# SparkFun_Thing_Plus_RA6M5.net
KiCad netlist of a schematic drawn in EAGLE
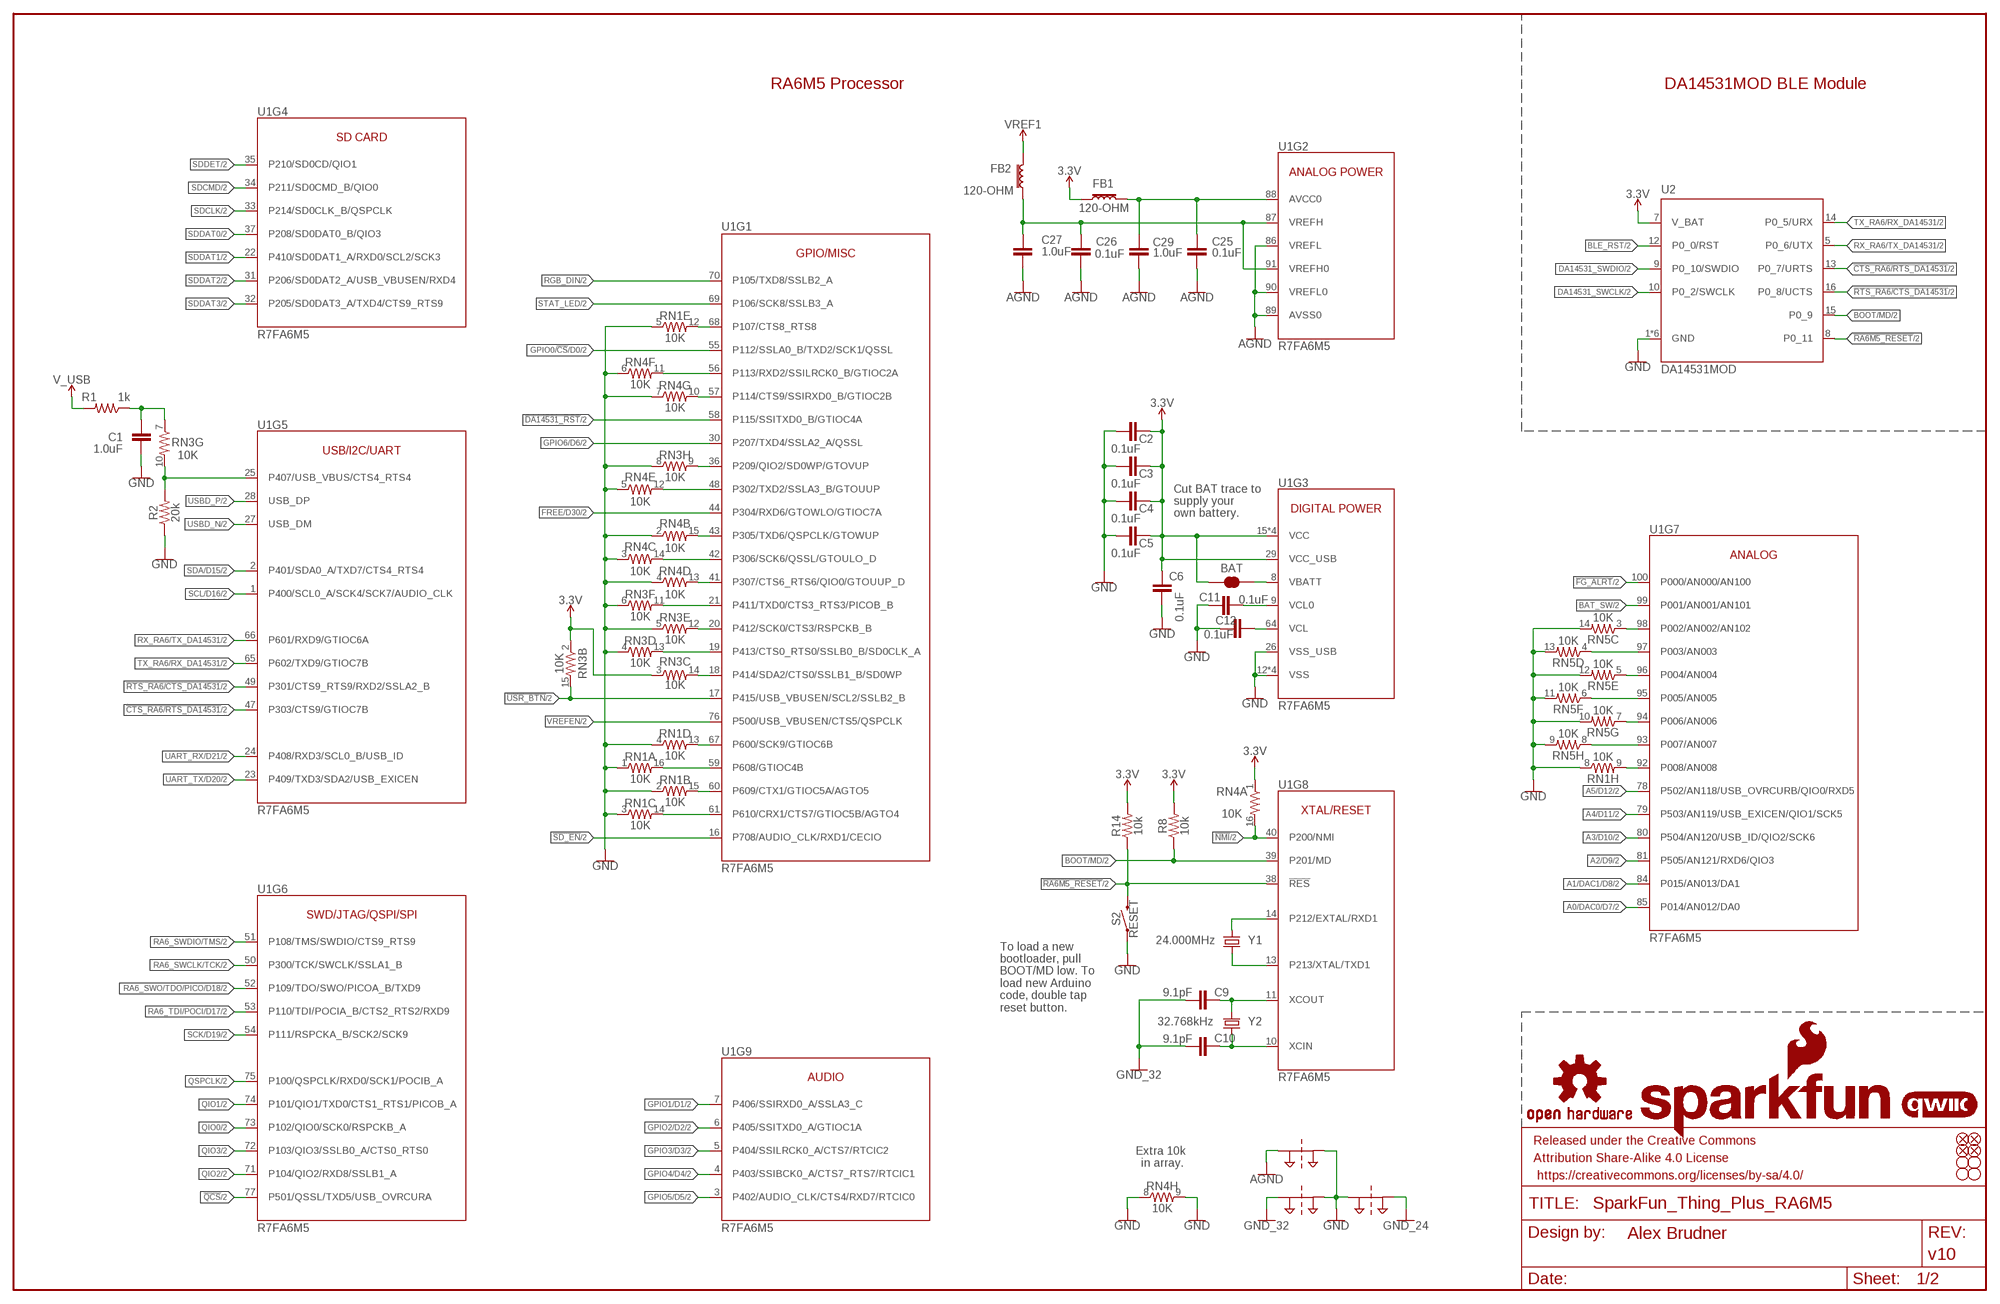
[diagram p0: schematic, sheet 1]
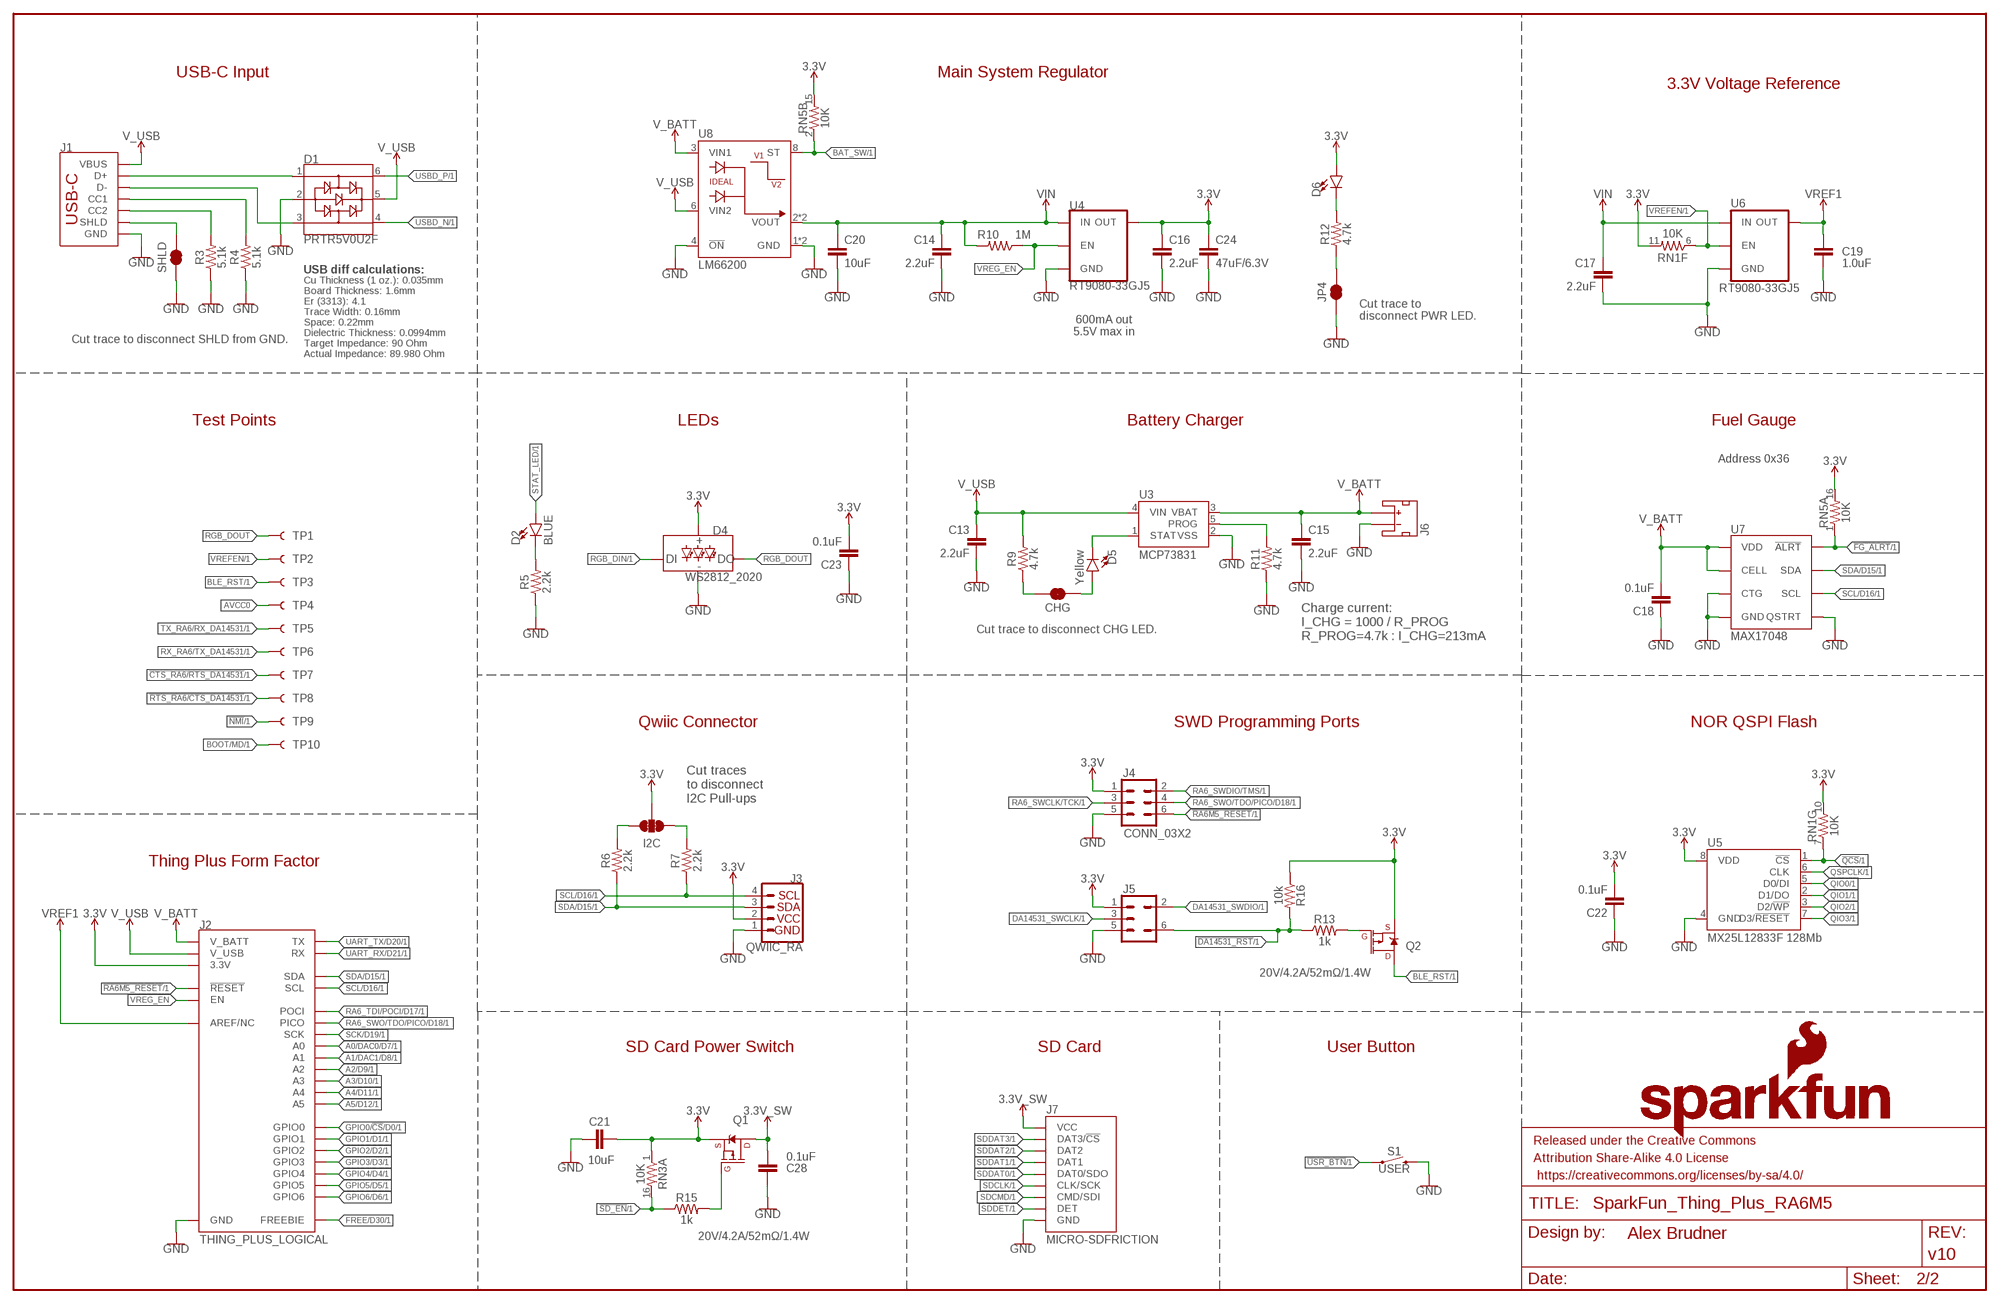
[diagram p1: schematic, sheet 2]

(export (version "E")
  (design (tool "Eeschema 10.0.6"))
  (components
    (comp (ref "C13")
      (value "2.2uF")
      (footprint "eagle-import:0402-TIGHT")
      (libsource (lib "eagle-import") (part "2.2UF-0402_TIGHT-10V-10%-X5R"))
    )
    (comp (ref "C14")
      (value "2.2uF")
      (footprint "eagle-import:0402-TIGHT")
      (libsource (lib "eagle-import") (part "2.2UF-0402_TIGHT-10V-10%-X5R"))
    )
    (comp (ref "C15")
      (value "2.2uF")
      (footprint "eagle-import:0402-TIGHT")
      (libsource (lib "eagle-import") (part "2.2UF-0402_TIGHT-10V-10%-X5R"))
    )
    (comp (ref "C16")
      (value "2.2uF")
      (footprint "eagle-import:0402-TIGHT")
      (libsource (lib "eagle-import") (part "2.2UF-0402_TIGHT-10V-10%-X5R"))
    )
    (comp (ref "C17")
      (value "2.2uF")
      (footprint "eagle-import:0402-TIGHT")
      (libsource (lib "eagle-import") (part "2.2UF-0402_TIGHT-10V-10%-X5R"))
    )
    (comp (ref "C18")
      (value "0.1uF")
      (footprint "eagle-import:0402-TIGHT")
      (libsource (lib "eagle-import") (part "0.1UF-0402T-16V-10%"))
    )
    (comp (ref "C19")
      (value "1.0uF")
      (footprint "eagle-import:0402-TIGHT")
      (libsource (lib "eagle-import") (part "1.0UF-0402T-16V-10%"))
    )
    (comp (ref "C20")
      (value "10uF")
      (footprint "eagle-import:0805")
      (libsource (lib "eagle-import") (part "10UF-0805-25V-10%"))
    )
    (comp (ref "C21")
      (value "10uF")
      (footprint "eagle-import:0805")
      (libsource (lib "eagle-import") (part "10UF-0805-25V-10%"))
    )
    (comp (ref "C22")
      (value "0.1uF")
      (footprint "eagle-import:0402-TIGHT")
      (libsource (lib "eagle-import") (part "0.1UF-0402T-16V-10%"))
    )
    (comp (ref "C23")
      (value "0.1uF")
      (footprint "eagle-import:0402-TIGHT")
      (libsource (lib "eagle-import") (part "0.1UF-0402T-16V-10%"))
    )
    (comp (ref "C24")
      (value "47uF/6.3V")
      (footprint "eagle-import:0805")
      (libsource (lib "eagle-import") (part "47UF"))
    )
    (comp (ref "C28")
      (value "0.1uF")
      (footprint "eagle-import:0402-TIGHT")
      (libsource (lib "eagle-import") (part "0.1UF-0402T-16V-10%"))
    )
    (comp (ref "CHG")
      (value "JUMPER-SMT_2_NC_TRACE_SILK")
      (footprint "eagle-import:SMT-JUMPER_2_NC_TRACE_SILK")
      (libsource (lib "eagle-import") (part "JUMPER-SMT_2_NC_TRACE_SILK"))
    )
    (comp (ref "D1")
      (value "PRTR5V0U2F")
      (footprint "eagle-import:SOT886")
      (libsource (lib "eagle-import") (part "PRTR5V0U2F"))
    )
    (comp (ref "D2")
      (value "BLUE")
      (footprint "eagle-import:LED-0603")
      (libsource (lib "eagle-import") (part "LED-BLUE0603"))
    )
    (comp (ref "D4")
      (value "WS2812_2020")
      (footprint "eagle-import:WS2812-2020")
      (libsource (lib "eagle-import") (part "WS2812_2020"))
    )
    (comp (ref "D5")
      (value "Yellow")
      (footprint "eagle-import:LED-0603")
      (libsource (lib "eagle-import") (part "LED-YELLOW0603"))
    )
    (comp (ref "D6")
      (value "LED-RED_0603-KB")
      (footprint "eagle-import:LED-0603")
      (libsource (lib "eagle-import") (part "LED-RED_0603-KB"))
    )
    (comp (ref "FRAME2")
      (value "FRAME-LEDGERNO_FOOTPRINT")
      (footprint "eagle-import:DUMMY")
      (fields (field (name "DESIGNER") "Alex Brudner") (field (name "REV") "v10"))
      (libsource (lib "eagle-import") (part "FRAME-LEDGERNO_FOOTPRINT"))
    )
    (comp (ref "I2C")
      (value "JUMPER-SMT_3_2-NC_TRACE_SILK")
      (footprint "eagle-import:SMT-JUMPER_3_2-NC_TRACE_SILK")
      (libsource (lib "eagle-import") (part "JUMPER-SMT_3_2-NC_TRACE_SILK"))
    )
    (comp (ref "J1")
      (value "USB Female Type C Connector")
      (footprint "eagle-import:USB-C-16P-6LAYER-ISOLATED")
      (libsource (lib "eagle-import") (part "USB_C_6-LAYER-ISOLATED"))
    )
    (comp (ref "J2")
      (value "THING_PLUS_LOGICAL")
      (footprint "eagle-import:THING_PLUS")
      (libsource (lib "eagle-import") (part "THING_PLUS_LOGICAL"))
    )
    (comp (ref "J3")
      (value "QWIIC_RA")
      (footprint "eagle-import:JST04_1MM_RA")
      (libsource (lib "eagle-import") (part "QWIIC_CONNECTORJS-1MM"))
    )
    (comp (ref "J4")
      (value "CONN_03X2")
      (footprint "eagle-import:PAD_05_03X2_TP")
      (libsource (lib "eagle-import") (part "CONN_03X2"))
    )
    (comp (ref "J5")
      (value "SWD-5PIN")
      (footprint "eagle-import:PAD_05_03X2_TP_NO4")
      (libsource (lib "eagle-import") (part "SWD-5PIN"))
    )
    (comp (ref "J6")
      (value "JST_2MM_MALE")
      (footprint "eagle-import:JST-2-SMD")
      (libsource (lib "eagle-import") (part "JST_2MM_MALE"))
    )
    (comp (ref "J7")
      (value "MICRO-SDFRICTION")
      (footprint "eagle-import:MICROSD_TINY")
      (libsource (lib "eagle-import") (part "MICRO-SDFRICTION"))
    )
    (comp (ref "JP4")
      (value "JUMPER-SMT_2_NC_TRACE_SILK")
      (footprint "eagle-import:SMT-JUMPER_2_NC_TRACE_SILK")
      (libsource (lib "eagle-import") (part "JUMPER-SMT_2_NC_TRACE_SILK"))
    )
    (comp (ref "LOGO4")
      (value "SFE_LOGO_NAME_FLAMEBLANK")
      (footprint "eagle-import:BLANK")
      (libsource (lib "eagle-import") (part "SFE_LOGO_NAME_FLAMEBLANK"))
    )
    (comp (ref "Q1")
      (value "20V/4.2A/52mΩ/1.4W")
      (footprint "eagle-import:SOT23-3")
      (libsource (lib "eagle-import") (part "MOSFET_PCH-DMG2305UX-7"))
    )
    (comp (ref "Q2")
      (value "20V/4.2A/52mΩ/1.4W")
      (footprint "eagle-import:SOT23-3")
      (libsource (lib "eagle-import") (part "MOSFET_PCH-DMG2305UX-7"))
    )
    (comp (ref "R3")
      (value "5.1k")
      (footprint "eagle-import:0402-TIGHT")
      (libsource (lib "eagle-import") (part "5.1KOHM-0402T-1/16W-1%"))
    )
    (comp (ref "R4")
      (value "5.1k")
      (footprint "eagle-import:0402-TIGHT")
      (libsource (lib "eagle-import") (part "5.1KOHM-0402T-1/16W-1%"))
    )
    (comp (ref "R5")
      (value "2.2k")
      (footprint "eagle-import:0402-TIGHT")
      (libsource (lib "eagle-import") (part "2.2KOHM-0402T-1/16W-1%"))
    )
    (comp (ref "R6")
      (value "2.2k")
      (footprint "eagle-import:0402-TIGHT")
      (libsource (lib "eagle-import") (part "2.2KOHM-0402T-1/16W-1%"))
    )
    (comp (ref "R7")
      (value "2.2k")
      (footprint "eagle-import:0402-TIGHT")
      (libsource (lib "eagle-import") (part "2.2KOHM-0402T-1/16W-1%"))
    )
    (comp (ref "R9")
      (value "4.7k")
      (footprint "eagle-import:0402-TIGHT")
      (libsource (lib "eagle-import") (part "4.7KOHM-0402T-1/16W-1%"))
    )
    (comp (ref "R10")
      (value "1M")
      (footprint "eagle-import:0402-TIGHT")
      (libsource (lib "eagle-import") (part "1MOHM-0402T-1/16W-5%"))
    )
    (comp (ref "R11")
      (value "4.7k")
      (footprint "eagle-import:0402-TIGHT")
      (libsource (lib "eagle-import") (part "4.7KOHM-0402T-1/16W-1%"))
    )
    (comp (ref "R12")
      (value "4.7k")
      (footprint "eagle-import:0402-TIGHT")
      (libsource (lib "eagle-import") (part "4.7KOHM-0402T-1/16W-1%"))
    )
    (comp (ref "R13")
      (value "1k")
      (footprint "eagle-import:0402-TIGHT")
      (libsource (lib "eagle-import") (part "1KOHM-0402T-1/16W-1%"))
    )
    (comp (ref "R15")
      (value "1k")
      (footprint "eagle-import:0402-TIGHT")
      (libsource (lib "eagle-import") (part "1KOHM-0402T-1/16W-1%"))
    )
    (comp (ref "R16")
      (value "10k")
      (footprint "eagle-import:0402-TIGHT")
      (libsource (lib "eagle-import") (part "10KOHM-0402T-1/16W-1%"))
    )
    (comp (ref "RN1")
      (value "10K")
      (footprint "eagle-import:2506_AR")
      (libsource (lib "eagle-import") (part "10KOHM-ARRAY(8)-2506_ARV-1/16W-5%"))
    )
    (comp (ref "RN3")
      (value "10K")
      (footprint "eagle-import:2506_AR")
      (libsource (lib "eagle-import") (part "10KOHM-ARRAY(8)-2506_ARV-1/16W-5%"))
    )
    (comp (ref "RN5")
      (value "10K")
      (footprint "eagle-import:2506_AR")
      (libsource (lib "eagle-import") (part "10KOHM-ARRAY(8)-2506_ARV-1/16W-5%"))
    )
    (comp (ref "S1")
      (value "USER")
      (footprint "eagle-import:TACTILE_SWITCH_SMD_4.6X2.8MM")
      (libsource (lib "eagle-import") (part "MOMENTARY-SWITCH-SPST-SMD-4.6X2.8MM"))
    )
    (comp (ref "SHLD")
      (value "JUMPER-SMT_2_NC_TRACE_SILK")
      (footprint "eagle-import:SMT-JUMPER_2_NC_TRACE_SILK")
      (libsource (lib "eagle-import") (part "JUMPER-SMT_2_NC_TRACE_SILK"))
    )
    (comp (ref "TP1")
      (value "TEST-POINT3X5")
      (footprint "eagle-import:PAD.03X.05")
      (libsource (lib "eagle-import") (part "TEST-POINT3X5"))
    )
    (comp (ref "TP2")
      (value "TEST-POINT3X4")
      (footprint "eagle-import:PAD.03X.04")
      (libsource (lib "eagle-import") (part "TEST-POINT3X4"))
    )
    (comp (ref "TP3")
      (value "TEST-POINT3X5")
      (footprint "eagle-import:PAD.03X.05")
      (libsource (lib "eagle-import") (part "TEST-POINT3X5"))
    )
    (comp (ref "TP4")
      (value "TEST-POINT3")
      (footprint "eagle-import:PAD.03X.03")
      (libsource (lib "eagle-import") (part "TEST-POINT3"))
    )
    (comp (ref "TP5")
      (value "TEST-POINT3X5")
      (footprint "eagle-import:PAD.03X.05")
      (libsource (lib "eagle-import") (part "TEST-POINT3X5"))
    )
    (comp (ref "TP6")
      (value "TEST-POINT3X5")
      (footprint "eagle-import:PAD.03X.05")
      (libsource (lib "eagle-import") (part "TEST-POINT3X5"))
    )
    (comp (ref "TP7")
      (value "TEST-POINT3X5")
      (footprint "eagle-import:PAD.03X.05")
      (libsource (lib "eagle-import") (part "TEST-POINT3X5"))
    )
    (comp (ref "TP8")
      (value "TEST-POINT3X5")
      (footprint "eagle-import:PAD.03X.05")
      (libsource (lib "eagle-import") (part "TEST-POINT3X5"))
    )
    (comp (ref "TP9")
      (value "TEST-POINT3")
      (footprint "eagle-import:PAD.03X.03")
      (libsource (lib "eagle-import") (part "TEST-POINT3"))
    )
    (comp (ref "TP10")
      (value "TEST-POINT3X5")
      (footprint "eagle-import:PAD.03X.05")
      (libsource (lib "eagle-import") (part "TEST-POINT3X5"))
    )
    (comp (ref "U3")
      (value "MCP73831")
      (footprint "eagle-import:SOT23-5")
      (libsource (lib "eagle-import") (part "MCP73831"))
    )
    (comp (ref "U4")
      (value "RT9080-33GJ5")
      (footprint "eagle-import:SOT23-5")
      (libsource (lib "eagle-import") (part "V_REG_RT9080"))
    )
    (comp (ref "U5")
      (value "MX25L12833F 128Mb")
      (footprint "eagle-import:WSON-8-6X5")
      (libsource (lib "eagle-import") (part "MX25L12833F_128MBIT_QSPI"))
    )
    (comp (ref "U6")
      (value "RT9080-33GJ5")
      (footprint "eagle-import:SOT23-5")
      (libsource (lib "eagle-import") (part "V_REG_RT9080"))
    )
    (comp (ref "U7")
      (value "MAX17048")
      (footprint "eagle-import:DFN-8")
      (libsource (lib "eagle-import") (part "MAX17048DFN8"))
    )
    (comp (ref "U8")
      (value "LM66200")
      (footprint "eagle-import:SOT8")
      (libsource (lib "eagle-import") (part "IDEAL_DIODE_DUAL_LM66200"))
    )
    (comp (ref "BAT")
      (value "JUMPER-SMT_2_NC_TRACE_SILK")
      (footprint "eagle-import:SMT-JUMPER_2_NC_TRACE_SILK")
      (libsource (lib "eagle-import") (part "JUMPER-SMT_2_NC_TRACE_SILK"))
    )
    (comp (ref "C1")
      (value "1.0uF")
      (footprint "eagle-import:0402-TIGHT")
      (libsource (lib "eagle-import") (part "1.0UF-0402T-16V-10%"))
    )
    (comp (ref "C2")
      (value "0.1uF")
      (footprint "eagle-import:0402-TIGHT")
      (libsource (lib "eagle-import") (part "0.1UF-0402T-16V-10%"))
    )
    (comp (ref "C3")
      (value "0.1uF")
      (footprint "eagle-import:0402-TIGHT")
      (libsource (lib "eagle-import") (part "0.1UF-0402T-16V-10%"))
    )
    (comp (ref "C4")
      (value "0.1uF")
      (footprint "eagle-import:0402-TIGHT")
      (libsource (lib "eagle-import") (part "0.1UF-0402T-16V-10%"))
    )
    (comp (ref "C5")
      (value "0.1uF")
      (footprint "eagle-import:0402-TIGHT")
      (libsource (lib "eagle-import") (part "0.1UF-0402T-16V-10%"))
    )
    (comp (ref "C6")
      (value "0.1uF")
      (footprint "eagle-import:0402-TIGHT")
      (libsource (lib "eagle-import") (part "0.1UF-0402T-16V-10%"))
    )
    (comp (ref "C9")
      (value "9.1pF")
      (footprint "eagle-import:0402-TIGHT")
      (fields (field (name "MOUSER_PART") "609-500R07S9R1CV4T"))
      (libsource (lib "eagle-import") (part "9.1PF-0402-TIGHT"))
    )
    (comp (ref "C10")
      (value "9.1pF")
      (footprint "eagle-import:0402-TIGHT")
      (fields (field (name "MOUSER_PART") "609-500R07S9R1CV4T"))
      (libsource (lib "eagle-import") (part "9.1PF-0402-TIGHT"))
    )
    (comp (ref "C11")
      (value "0.1uF")
      (footprint "eagle-import:0402-TIGHT")
      (libsource (lib "eagle-import") (part "0.1UF-0402T-16V-10%"))
    )
    (comp (ref "C12")
      (value "0.1uF")
      (footprint "eagle-import:0402-TIGHT")
      (libsource (lib "eagle-import") (part "0.1UF-0402T-16V-10%"))
    )
    (comp (ref "C25")
      (value "0.1uF")
      (footprint "eagle-import:0402-TIGHT")
      (libsource (lib "eagle-import") (part "0.1UF-0402T-16V-10%"))
    )
    (comp (ref "C26")
      (value "0.1uF")
      (footprint "eagle-import:0402-TIGHT")
      (libsource (lib "eagle-import") (part "0.1UF-0402T-16V-10%"))
    )
    (comp (ref "C27")
      (value "1.0uF")
      (footprint "eagle-import:0402-TIGHT")
      (libsource (lib "eagle-import") (part "1.0UF-0402T-16V-10%"))
    )
    (comp (ref "C29")
      (value "1.0uF")
      (footprint "eagle-import:0402-TIGHT")
      (libsource (lib "eagle-import") (part "1.0UF-0402T-16V-10%"))
    )
    (comp (ref "FB1")
      (value "120-OHM")
      (footprint "eagle-import:0402-TIGHT")
      (libsource (lib "eagle-import") (part "FERRITE_BEAD-120_OHM-0402T"))
    )
    (comp (ref "FB2")
      (value "120-OHM")
      (footprint "eagle-import:0402-TIGHT")
      (libsource (lib "eagle-import") (part "FERRITE_BEAD-120_OHM-0402T"))
    )
    (comp (ref "FD1")
      (value "FIDUCIALUFIDUCIAL")
      (footprint "eagle-import:FIDUCIAL-MICRO")
      (libsource (lib "eagle-import") (part "FIDUCIALUFIDUCIAL"))
    )
    (comp (ref "FD2")
      (value "FIDUCIALUFIDUCIAL")
      (footprint "eagle-import:FIDUCIAL-MICRO")
      (libsource (lib "eagle-import") (part "FIDUCIALUFIDUCIAL"))
    )
    (comp (ref "FD3")
      (value "FIDUCIALUFIDUCIAL")
      (footprint "eagle-import:FIDUCIAL-MICRO")
      (libsource (lib "eagle-import") (part "FIDUCIALUFIDUCIAL"))
    )
    (comp (ref "FD4")
      (value "FIDUCIALUFIDUCIAL")
      (footprint "eagle-import:FIDUCIAL-MICRO")
      (libsource (lib "eagle-import") (part "FIDUCIALUFIDUCIAL"))
    )
    (comp (ref "FRAME1")
      (value "FRAME-LEDGER")
      (footprint "eagle-import:CREATIVE_COMMONS")
      (fields (field (name "DESIGNER") "Alex Brudner") (field (name "REV") "v10"))
      (libsource (lib "eagle-import") (part "FRAME-LEDGER"))
    )
    (comp (ref "H1")
      (value "STAND-OFFTIGHT")
      (footprint "eagle-import:STAND-OFF-TIGHT")
      (libsource (lib "eagle-import") (part "STAND-OFFTIGHT"))
    )
    (comp (ref "H2")
      (value "STAND-OFFTIGHT")
      (footprint "eagle-import:STAND-OFF-TIGHT")
      (libsource (lib "eagle-import") (part "STAND-OFFTIGHT"))
    )
    (comp (ref "H3")
      (value "STAND-OFFTIGHT")
      (footprint "eagle-import:STAND-OFF-TIGHT")
      (libsource (lib "eagle-import") (part "STAND-OFFTIGHT"))
    )
    (comp (ref "H4")
      (value "STAND-OFFTIGHT")
      (footprint "eagle-import:STAND-OFF-TIGHT")
      (libsource (lib "eagle-import") (part "STAND-OFFTIGHT"))
    )
    (comp (ref "LOGO1")
      (value "OSHW-LOGOMINI")
      (footprint "eagle-import:OSHW-LOGO-MINI")
      (libsource (lib "eagle-import") (part "OSHW-LOGOMINI"))
    )
    (comp (ref "LOGO2")
      (value "SFE_LOGO_NAME_FLAME.1_INCH")
      (footprint "eagle-import:SFE_LOGO_NAME_FLAME_.1")
      (libsource (lib "eagle-import") (part "SFE_LOGO_NAME_FLAME.1_INCH"))
    )
    (comp (ref "LOGO3")
      (value "QWIIC_LOGO_4MM")
      (footprint "eagle-import:QWIIC_4MM")
      (libsource (lib "eagle-import") (part "QWIIC_LOGO_4MM"))
    )
    (comp (ref "R1")
      (value "1k")
      (footprint "eagle-import:0402-TIGHT")
      (libsource (lib "eagle-import") (part "1KOHM-0402T-1/16W-1%"))
    )
    (comp (ref "R2")
      (value "20k")
      (footprint "eagle-import:0402-TIGHT")
      (libsource (lib "eagle-import") (part "20KOHM-0402T-1/16W-1%"))
    )
    (comp (ref "R8")
      (value "10k")
      (footprint "eagle-import:0402-TIGHT")
      (libsource (lib "eagle-import") (part "10KOHM-0402T-1/16W-1%"))
    )
    (comp (ref "R14")
      (value "10k")
      (footprint "eagle-import:0402-TIGHT")
      (libsource (lib "eagle-import") (part "10KOHM-0402T-1/16W-1%"))
    )
    (comp (ref "RN4")
      (value "10K")
      (footprint "eagle-import:2506_AR")
      (libsource (lib "eagle-import") (part "10KOHM-ARRAY(8)-2506_ARV-1/16W-5%"))
    )
    (comp (ref "S2")
      (value "RESET")
      (footprint "eagle-import:TACTILE_SWITCH_SMD_4.6X2.8MM")
      (libsource (lib "eagle-import") (part "MOMENTARY-SWITCH-SPST-SMD-4.6X2.8MM"))
    )
    (comp (ref "SUPPLYTIE1")
      (value "2PT_GND_TIESMALL")
      (footprint "eagle-import:2PT_GND_TIE_SMALL")
      (libsource (lib "eagle-import") (part "2PT_GND_TIESMALL"))
    )
    (comp (ref "SUPPLYTIE2")
      (value "2PT_GND_TIESMALL")
      (footprint "eagle-import:2PT_GND_TIE_SMALL")
      (libsource (lib "eagle-import") (part "2PT_GND_TIESMALL"))
    )
    (comp (ref "SUPPLYTIE3")
      (value "2PT_GND_TIESMALL")
      (footprint "eagle-import:2PT_GND_TIE_SMALL")
      (libsource (lib "eagle-import") (part "2PT_GND_TIESMALL"))
    )
    (comp (ref "U1")
      (value "R7FA6M5")
      (footprint "eagle-import:P-LQFP100-14X14-0.50")
      (libsource (lib "eagle-import") (part "R7FA6M5-100LQFP"))
    )
    (comp (ref "U2")
      (value "DA14531MOD")
      (footprint "eagle-import:DA14531MOD")
      (libsource (lib "eagle-import") (part "DA14531MOD"))
    )
    (comp (ref "Y1")
      (value "24.000MHz")
      (footprint "eagle-import:4-SMD,32X25")
      (libsource (lib "eagle-import") (part "CRYSTAL-24.000MHZ-8PF-4-SMD"))
    )
    (comp (ref "Y2")
      (value "32.768kHz")
      (footprint "eagle-import:CRYSTAL-SMD-3.2X1.5MM")
      (libsource (lib "eagle-import") (part "CRYSTAL-32.768KHZSMD-3.2X1.5"))
    )
  )
  (nets
    (net (code "1") (name "3.3V") (class "Default")
      (node (ref "BAT") (pin "1") (pinfunction "1_1") (pintype "passive"))
      (node (ref "C16") (pin "1") (pinfunction "1_1") (pintype "passive"))
      (node (ref "C2") (pin "1") (pinfunction "1_1") (pintype "passive"))
      (node (ref "C21") (pin "1") (pinfunction "1_1") (pintype "passive"))
      (node (ref "C22") (pin "2") (pinfunction "2_2") (pintype "passive"))
      (node (ref "C23") (pin "2") (pinfunction "2_2") (pintype "passive"))
      (node (ref "C24") (pin "1") (pinfunction "1_1") (pintype "passive"))
      (node (ref "C3") (pin "1") (pinfunction "1_1") (pintype "passive"))
      (node (ref "C4") (pin "1") (pinfunction "1_1") (pintype "passive"))
      (node (ref "C5") (pin "1") (pinfunction "1_1") (pintype "passive"))
      (node (ref "C6") (pin "1") (pinfunction "1_1") (pintype "passive"))
      (node (ref "D4") (pin "VCC") (pinfunction "VCC_VCC") (pintype "bidirectional"))
      (node (ref "D6") (pin "A") (pinfunction "A_A") (pintype "passive"))
      (node (ref "FB1") (pin "1") (pinfunction "1_1") (pintype "passive"))
      (node (ref "I2C") (pin "2") (pinfunction "2_2") (pintype "passive"))
      (node (ref "J2") (pin "27") (pinfunction "3.3V_27") (pintype "bidirectional"))
      (node (ref "J3") (pin "2") (pinfunction "2_2") (pintype "power_in"))
      (node (ref "J4") (pin "1") (pinfunction "1_1") (pintype "bidirectional"))
      (node (ref "J5") (pin "1") (pinfunction "1_1") (pintype "bidirectional"))
      (node (ref "Q1") (pin "2") (pinfunction "S_2") (pintype "bidirectional"))
      (node (ref "Q2") (pin "2") (pinfunction "S_2") (pintype "bidirectional"))
      (node (ref "R14") (pin "2") (pinfunction "2_2") (pintype "passive"))
      (node (ref "R16") (pin "1") (pinfunction "1_1") (pintype "passive"))
      (node (ref "R8") (pin "2") (pinfunction "2_2") (pintype "passive"))
      (node (ref "RN1") (pin "10") (pinfunction "2_10") (pintype "passive"))
      (node (ref "RN1") (pin "11") (pinfunction "2_11") (pintype "passive"))
      (node (ref "RN3") (pin "1") (pinfunction "1_1") (pintype "passive"))
      (node (ref "RN3") (pin "2") (pinfunction "1_2") (pintype "passive"))
      (node (ref "RN3") (pin "3") (pinfunction "1_3") (pintype "passive"))
      (node (ref "RN4") (pin "1") (pinfunction "1_1") (pintype "passive"))
      (node (ref "RN5") (pin "15") (pinfunction "2_15") (pintype "passive"))
      (node (ref "RN5") (pin "16") (pinfunction "2_16") (pintype "passive"))
      (node (ref "U1") (pin "15") (pinfunction "VCC_15") (pintype "bidirectional"))
      (node (ref "U1") (pin "29") (pinfunction "VCC_USB_29") (pintype "bidirectional"))
      (node (ref "U1") (pin "46") (pinfunction "VCC_46") (pintype "bidirectional"))
      (node (ref "U1") (pin "62") (pinfunction "VCC_62") (pintype "bidirectional"))
      (node (ref "U1") (pin "82") (pinfunction "VCC_82") (pintype "bidirectional"))
      (node (ref "U2") (pin "7") (pinfunction "V_BAT_7") (pintype "bidirectional"))
      (node (ref "U4") (pin "5") (pinfunction "OUT_5") (pintype "passive"))
      (node (ref "U5") (pin "8") (pinfunction "VDD_8") (pintype "bidirectional"))
    )
    (net (code "2") (name "3.3V_SW") (class "Default")
      (node (ref "C28") (pin "2") (pinfunction "2_2") (pintype "passive"))
      (node (ref "J7") (pin "4") (pinfunction "VCC_4") (pintype "bidirectional"))
      (node (ref "Q1") (pin "3") (pinfunction "D_3") (pintype "bidirectional"))
    )
    (net (code "3") (name "A0{slash}DAC0{slash}D7") (class "Default")
      (node (ref "J2") (pin "24") (pinfunction "A0_24") (pintype "bidirectional"))
      (node (ref "U1") (pin "85") (pinfunction "P014/AN012/DA0_85") (pintype "bidirectional"))
    )
    (net (code "4") (name "A1{slash}DAC1{slash}D8") (class "Default")
      (node (ref "J2") (pin "23") (pinfunction "A1_23") (pintype "bidirectional"))
      (node (ref "U1") (pin "84") (pinfunction "P015/AN013/DA1_84") (pintype "bidirectional"))
    )
    (net (code "5") (name "A2{slash}D9") (class "Default")
      (node (ref "J2") (pin "22") (pinfunction "A2_22") (pintype "bidirectional"))
      (node (ref "U1") (pin "81") (pinfunction "P505/AN121/RXD6/QIO3_81") (pintype "bidirectional"))
    )
    (net (code "6") (name "A3{slash}D10") (class "Default")
      (node (ref "J2") (pin "21") (pinfunction "A3_21") (pintype "bidirectional"))
      (node (ref "U1") (pin "80") (pinfunction "P504/AN120/USB_ID/QIO2/SCK6_80") (pintype "bidirectional"))
    )
    (net (code "7") (name "A4{slash}D11") (class "Default")
      (node (ref "J2") (pin "20") (pinfunction "A4_20") (pintype "bidirectional"))
      (node (ref "U1") (pin "79") (pinfunction "P503/AN119/USB_EXICEN/QIO1/SCK5_79") (pintype "bidirectional"))
    )
    (net (code "8") (name "A5{slash}D12") (class "Default")
      (node (ref "J2") (pin "19") (pinfunction "A5_19") (pintype "bidirectional"))
      (node (ref "U1") (pin "78") (pinfunction "P502/AN118/USB_OVRCURB/QIO0/RXD5_78") (pintype "bidirectional"))
    )
    (net (code "9") (name "AGND") (class "Default")
      (node (ref "C25") (pin "2") (pinfunction "2_2") (pintype "passive"))
      (node (ref "C26") (pin "2") (pinfunction "2_2") (pintype "passive"))
      (node (ref "C27") (pin "2") (pinfunction "2_2") (pintype "passive"))
      (node (ref "C29") (pin "2") (pinfunction "2_2") (pintype "passive"))
      (node (ref "SUPPLYTIE1") (pin "P$1") (pinfunction "P$1_P$1") (pintype "bidirectional"))
      (node (ref "U1") (pin "86") (pinfunction "VREFL_86") (pintype "bidirectional"))
      (node (ref "U1") (pin "89") (pinfunction "AVSS0_89") (pintype "bidirectional"))
      (node (ref "U1") (pin "90") (pinfunction "VREFL0_90") (pintype "bidirectional"))
    )
    (net (code "10") (name "AVCC0") (class "Default")
      (node (ref "C25") (pin "1") (pinfunction "1_1") (pintype "passive"))
      (node (ref "C29") (pin "1") (pinfunction "1_1") (pintype "passive"))
      (node (ref "FB1") (pin "2") (pinfunction "2_2") (pintype "passive"))
      (node (ref "TP4") (pin "1") (pinfunction "1_1") (pintype "bidirectional"))
      (node (ref "U1") (pin "88") (pinfunction "AVCC0_88") (pintype "bidirectional"))
    )
    (net (code "11") (name "BAT_SW") (class "Default")
      (node (ref "RN5") (pin "2") (pinfunction "1_2") (pintype "passive"))
      (node (ref "U1") (pin "99") (pinfunction "P001/AN001/AN101_99") (pintype "bidirectional"))
      (node (ref "U8") (pin "8") (pinfunction "ST_8") (pintype "bidirectional"))
    )
    (net (code "12") (name "BLE_RST") (class "Default")
      (node (ref "Q2") (pin "3") (pinfunction "D_3") (pintype "bidirectional"))
      (node (ref "TP3") (pin "1") (pinfunction "1_1") (pintype "bidirectional"))
      (node (ref "U2") (pin "12") (pinfunction "P0_0/RST_12") (pintype "bidirectional"))
    )
    (net (code "13") (name "BOOT{slash}MD") (class "Default")
      (node (ref "R8") (pin "1") (pinfunction "1_1") (pintype "passive"))
      (node (ref "TP10") (pin "1") (pinfunction "1_1") (pintype "bidirectional"))
      (node (ref "U1") (pin "39") (pinfunction "P201/MD_39") (pintype "bidirectional"))
      (node (ref "U2") (pin "15") (pinfunction "P0_9_15") (pintype "bidirectional"))
    )
    (net (code "14") (name "DA14531_SWCLK") (class "Default")
      (node (ref "J5") (pin "3") (pinfunction "3_3") (pintype "bidirectional"))
      (node (ref "U2") (pin "10") (pinfunction "P0_2/SWCLK_10") (pintype "bidirectional"))
    )
    (net (code "15") (name "DA14531_SWDIO") (class "Default")
      (node (ref "J5") (pin "2") (pinfunction "2_2") (pintype "bidirectional"))
      (node (ref "U2") (pin "9") (pinfunction "P0_10/SWDIO_9") (pintype "bidirectional"))
    )
    (net (code "16") (name "FREE{slash}D30") (class "Default")
      (node (ref "J2") (pin "13") (pinfunction "FREEBIE_13") (pintype "bidirectional"))
      (node (ref "U1") (pin "44") (pinfunction "P304/RXD6/GTOWLO/GTIOC7A_44") (pintype "bidirectional"))
    )
    (net (code "17") (name "GND") (class "Default")
      (node (ref "C1") (pin "1") (pinfunction "1_1") (pintype "passive"))
      (node (ref "C11") (pin "2") (pinfunction "2_2") (pintype "passive"))
      (node (ref "C12") (pin "2") (pinfunction "2_2") (pintype "passive"))
      (node (ref "C13") (pin "2") (pinfunction "2_2") (pintype "passive"))
      (node (ref "C14") (pin "2") (pinfunction "2_2") (pintype "passive"))
      (node (ref "C15") (pin "2") (pinfunction "2_2") (pintype "passive"))
      (node (ref "C16") (pin "2") (pinfunction "2_2") (pintype "passive"))
      (node (ref "C17") (pin "2") (pinfunction "2_2") (pintype "passive"))
      (node (ref "C18") (pin "1") (pinfunction "1_1") (pintype "passive"))
      (node (ref "C19") (pin "2") (pinfunction "2_2") (pintype "passive"))
      (node (ref "C2") (pin "2") (pinfunction "2_2") (pintype "passive"))
      (node (ref "C20") (pin "2") (pinfunction "2_2") (pintype "passive"))
      (node (ref "C21") (pin "2") (pinfunction "2_2") (pintype "passive"))
      (node (ref "C22") (pin "1") (pinfunction "1_1") (pintype "passive"))
      (node (ref "C23") (pin "1") (pinfunction "1_1") (pintype "passive"))
      (node (ref "C24") (pin "2") (pinfunction "2_2") (pintype "passive"))
      (node (ref "C28") (pin "1") (pinfunction "1_1") (pintype "passive"))
      (node (ref "C3") (pin "2") (pinfunction "2_2") (pintype "passive"))
      (node (ref "C4") (pin "2") (pinfunction "2_2") (pintype "passive"))
      (node (ref "C5") (pin "2") (pinfunction "2_2") (pintype "passive"))
      (node (ref "C6") (pin "2") (pinfunction "2_2") (pintype "passive"))
      (node (ref "D1") (pin "2") (pinfunction "2_2") (pintype "power_in"))
      (node (ref "D4") (pin "GND") (pinfunction "GND_GND") (pintype "bidirectional"))
      (node (ref "J1") (pin "GND") (pinfunction "GND_GND") (pintype "bidirectional"))
      (node (ref "J1") (pin "GND2") (pinfunction "GND_GND2") (pintype "bidirectional"))
      (node (ref "J2") (pin "25") (pinfunction "GND_25") (pintype "bidirectional"))
      (node (ref "J3") (pin "1") (pinfunction "1_1") (pintype "power_in"))
      (node (ref "J4") (pin "5") (pinfunction "5_5") (pintype "bidirectional"))
      (node (ref "J5") (pin "5") (pinfunction "5_5") (pintype "bidirectional"))
      (node (ref "J6") (pin "1") (pinfunction "-_1") (pintype "bidirectional"))
      (node (ref "J7") (pin "6") (pinfunction "GND_6") (pintype "bidirectional"))
      (node (ref "J7") (pin "GND1") (pinfunction "GND_GND1") (pintype "bidirectional"))
      (node (ref "J7") (pin "GND2") (pinfunction "GND_GND2") (pintype "bidirectional"))
      (node (ref "J7") (pin "GND3") (pinfunction "GND_GND3") (pintype "bidirectional"))
      (node (ref "J7") (pin "GND4") (pinfunction "GND_GND4") (pintype "bidirectional"))
      (node (ref "J7") (pin "GND5") (pinfunction "GND_GND5") (pintype "bidirectional"))
      (node (ref "J7") (pin "GND6") (pinfunction "GND_GND6") (pintype "bidirectional"))
      (node (ref "JP4") (pin "1") (pinfunction "1_1") (pintype "passive"))
      (node (ref "R11") (pin "1") (pinfunction "1_1") (pintype "passive"))
      (node (ref "R2") (pin "1") (pinfunction "1_1") (pintype "passive"))
      (node (ref "R3") (pin "1") (pinfunction "1_1") (pintype "passive"))
      (node (ref "R4") (pin "1") (pinfunction "1_1") (pintype "passive"))
      (node (ref "R5") (pin "1") (pinfunction "1_1") (pintype "passive"))
      (node (ref "RN1") (pin "1") (pinfunction "1_1") (pintype "passive"))
      (node (ref "RN1") (pin "2") (pinfunction "1_2") (pintype "passive"))
      (node (ref "RN1") (pin "3") (pinfunction "1_3") (pintype "passive"))
      (node (ref "RN1") (pin "4") (pinfunction "1_4") (pintype "passive"))
      (node (ref "RN1") (pin "5") (pinfunction "1_5") (pintype "passive"))
      (node (ref "RN1") (pin "8") (pinfunction "1_8") (pintype "passive"))
      (node (ref "RN3") (pin "4") (pinfunction "1_4") (pintype "passive"))
      (node (ref "RN3") (pin "5") (pinfunction "1_5") (pintype "passive"))
      (node (ref "RN3") (pin "6") (pinfunction "1_6") (pintype "passive"))
      (node (ref "RN3") (pin "8") (pinfunction "1_8") (pintype "passive"))
      (node (ref "RN4") (pin "2") (pinfunction "1_2") (pintype "passive"))
      (node (ref "RN4") (pin "3") (pinfunction "1_3") (pintype "passive"))
      (node (ref "RN4") (pin "4") (pinfunction "1_4") (pintype "passive"))
      (node (ref "RN4") (pin "5") (pinfunction "1_5") (pintype "passive"))
      (node (ref "RN4") (pin "6") (pinfunction "1_6") (pintype "passive"))
      (node (ref "RN4") (pin "7") (pinfunction "1_7") (pintype "passive"))
      (node (ref "RN4") (pin "8") (pinfunction "1_8") (pintype "passive"))
      (node (ref "RN4") (pin "9") (pinfunction "2_9") (pintype "passive"))
      (node (ref "RN5") (pin "10") (pinfunction "2_10") (pintype "passive"))
      (node (ref "RN5") (pin "11") (pinfunction "2_11") (pintype "passive"))
      (node (ref "RN5") (pin "12") (pinfunction "2_12") (pintype "passive"))
      (node (ref "RN5") (pin "13") (pinfunction "2_13") (pintype "passive"))
      (node (ref "RN5") (pin "14") (pinfunction "2_14") (pintype "passive"))
      (node (ref "RN5") (pin "9") (pinfunction "2_9") (pintype "passive"))
      (node (ref "S1") (pin "3") (pinfunction "2_3") (pintype "passive"))
      (node (ref "S1") (pin "4") (pinfunction "2_4") (pintype "passive"))
      (node (ref "S2") (pin "1") (pinfunction "1_1") (pintype "passive"))
      (node (ref "S2") (pin "2") (pinfunction "1_2") (pintype "passive"))
      (node (ref "SHLD") (pin "1") (pinfunction "1_1") (pintype "passive"))
      (node (ref "SUPPLYTIE1") (pin "P$2") (pinfunction "P$2_P$2") (pintype "bidirectional"))
      (node (ref "SUPPLYTIE2") (pin "P$2") (pinfunction "P$2_P$2") (pintype "bidirectional"))
      (node (ref "SUPPLYTIE3") (pin "P$1") (pinfunction "P$1_P$1") (pintype "bidirectional"))
      (node (ref "U1") (pin "12") (pinfunction "VSS_12") (pintype "bidirectional"))
      (node (ref "U1") (pin "26") (pinfunction "VSS_USB_26") (pintype "bidirectional"))
      (node (ref "U1") (pin "45") (pinfunction "VSS_45") (pintype "bidirectional"))
      (node (ref "U1") (pin "63") (pinfunction "VSS_63") (pintype "bidirectional"))
      (node (ref "U1") (pin "83") (pinfunction "VSS_83") (pintype "bidirectional"))
      (node (ref "U2") (pin "1") (pinfunction "GND_1") (pintype "bidirectional"))
      (node (ref "U2") (pin "11") (pinfunction "GND_11") (pintype "bidirectional"))
      (node (ref "U2") (pin "2") (pinfunction "GND_2") (pintype "bidirectional"))
      (node (ref "U2") (pin "3") (pinfunction "GND_3") (pintype "bidirectional"))
      (node (ref "U2") (pin "4") (pinfunction "GND_4") (pintype "bidirectional"))
      (node (ref "U2") (pin "6") (pinfunction "GND_6") (pintype "bidirectional"))
      (node (ref "U3") (pin "2") (pinfunction "VSS_2") (pintype "power_in"))
      (node (ref "U4") (pin "2") (pinfunction "GND_2") (pintype "input"))
      (node (ref "U5") (pin "4") (pinfunction "GND_4") (pintype "bidirectional"))
      (node (ref "U6") (pin "2") (pinfunction "GND_2") (pintype "input"))
      (node (ref "U7") (pin "1") (pinfunction "CTG_1") (pintype "input"))
      (node (ref "U7") (pin "4") (pinfunction "GND_4") (pintype "bidirectional"))
      (node (ref "U7") (pin "6") (pinfunction "QSTRT_6") (pintype "bidirectional"))
      (node (ref "U7") (pin "9") (pinfunction "GND_9") (pintype "bidirectional"))
      (node (ref "U8") (pin "1") (pinfunction "GND_1") (pintype "bidirectional"))
      (node (ref "U8") (pin "4") (pinfunction "~{ON}_4") (pintype "bidirectional"))
      (node (ref "U8") (pin "5") (pinfunction "GND_5") (pintype "bidirectional"))
    )
    (net (code "18") (name "GND_24") (class "Default")
      (node (ref "SUPPLYTIE3") (pin "P$2") (pinfunction "P$2_P$2") (pintype "bidirectional"))
    )
    (net (code "19") (name "GND_32") (class "Default")
      (node (ref "C10") (pin "1") (pinfunction "1_1") (pintype "passive"))
      (node (ref "C9") (pin "1") (pinfunction "1_1") (pintype "passive"))
      (node (ref "SUPPLYTIE2") (pin "P$1") (pinfunction "P$1_P$1") (pintype "bidirectional"))
    )
    (net (code "20") (name "GPIO0{slash}~{CS}{slash}D0") (class "Default")
      (node (ref "J2") (pin "9") (pinfunction "GPIO0_9") (pintype "bidirectional"))
      (node (ref "U1") (pin "55") (pinfunction "P112/SSLA0_B/TXD2/SCK1/QSSL_55") (pintype "bidirectional"))
    )
    (net (code "21") (name "GPIO1{slash}D1") (class "Default")
      (node (ref "J2") (pin "8") (pinfunction "GPIO1_8") (pintype "bidirectional"))
      (node (ref "U1") (pin "7") (pinfunction "P406/SSIRXD0_A/SSLA3_C_7") (pintype "bidirectional"))
    )
    (net (code "22") (name "GPIO2{slash}D2") (class "Default")
      (node (ref "J2") (pin "7") (pinfunction "GPIO2_7") (pintype "bidirectional"))
      (node (ref "U1") (pin "6") (pinfunction "P405/SSITXD0_A/GTIOC1A_6") (pintype "bidirectional"))
    )
    (net (code "23") (name "GPIO3{slash}D3") (class "Default")
      (node (ref "J2") (pin "6") (pinfunction "GPIO3_6") (pintype "bidirectional"))
      (node (ref "U1") (pin "5") (pinfunction "P404/SSILRCK0_A/CTS7/RTCIC2_5") (pintype "bidirectional"))
    )
    (net (code "24") (name "GPIO4{slash}D4") (class "Default")
      (node (ref "J2") (pin "5") (pinfunction "GPIO4_5") (pintype "bidirectional"))
      (node (ref "U1") (pin "4") (pinfunction "P403/SSIBCK0_A/CTS7_RTS7/RTCIC1_4") (pintype "bidirectional"))
    )
    (net (code "25") (name "GPIO5{slash}D5") (class "Default")
      (node (ref "J2") (pin "4") (pinfunction "GPIO5_4") (pintype "bidirectional"))
      (node (ref "U1") (pin "3") (pinfunction "P402/AUDIO_CLK/CTS4/RXD7/RTCIC0_3") (pintype "bidirectional"))
    )
    (net (code "26") (name "GPIO6{slash}D6") (class "Default")
      (node (ref "J2") (pin "3") (pinfunction "GPIO6_3") (pintype "bidirectional"))
      (node (ref "U1") (pin "30") (pinfunction "P207/TXD4/SSLA2_A/QSSL_30") (pintype "bidirectional"))
    )
    (net (code "27") (name "Net-(CHG-Pad1)") (class "Default")
      (node (ref "CHG") (pin "1") (pinfunction "1_1") (pintype "passive"))
      (node (ref "D5") (pin "A") (pinfunction "A_A") (pintype "passive"))
    )
    (net (code "28") (name "Net-(CHG-Pad2)") (class "Default")
      (node (ref "CHG") (pin "2") (pinfunction "2_2") (pintype "passive"))
      (node (ref "R9") (pin "1") (pinfunction "1_1") (pintype "passive"))
    )
    (net (code "29") (name "Net-(D1-Pad1)") (class "Default")
      (node (ref "D1") (pin "1") (pinfunction "1_1") (pintype "bidirectional"))
      (node (ref "J1") (pin "A6") (pinfunction "D+_A6") (pintype "bidirectional"))
      (node (ref "J1") (pin "B6") (pinfunction "D+_B6") (pintype "bidirectional"))
    )
    (net (code "30") (name "Net-(D1-Pad3)") (class "Default")
      (node (ref "D1") (pin "3") (pinfunction "3_3") (pintype "bidirectional"))
      (node (ref "J1") (pin "A7") (pinfunction "D-_A7") (pintype "bidirectional"))
      (node (ref "J1") (pin "B7") (pinfunction "D-_B7") (pintype "bidirectional"))
    )
    (net (code "31") (name "Net-(D2-PadC)") (class "Default")
      (node (ref "D2") (pin "C") (pinfunction "C_C") (pintype "passive"))
      (node (ref "R5") (pin "2") (pinfunction "2_2") (pintype "passive"))
    )
    (net (code "32") (name "Net-(D6-PadC)") (class "Default")
      (node (ref "D6") (pin "C") (pinfunction "C_C") (pintype "passive"))
      (node (ref "R12") (pin "2") (pinfunction "2_2") (pintype "passive"))
    )
    (net (code "33") (name "Net-(I2C-Pad1)") (class "Default")
      (node (ref "I2C") (pin "1") (pinfunction "1_1") (pintype "passive"))
      (node (ref "R6") (pin "2") (pinfunction "2_2") (pintype "passive"))
    )
    (net (code "34") (name "Net-(I2C-Pad3)") (class "Default")
      (node (ref "I2C") (pin "3") (pinfunction "3_3") (pintype "passive"))
      (node (ref "R7") (pin "2") (pinfunction "2_2") (pintype "passive"))
    )
    (net (code "35") (name "Net-(J1-CC1)") (class "Default")
      (node (ref "J1") (pin "A5") (pinfunction "CC1_A5") (pintype "bidirectional"))
      (node (ref "R4") (pin "2") (pinfunction "2_2") (pintype "passive"))
    )
    (net (code "36") (name "Net-(J1-CC2)") (class "Default")
      (node (ref "J1") (pin "B5") (pinfunction "CC2_B5") (pintype "bidirectional"))
      (node (ref "R3") (pin "2") (pinfunction "2_2") (pintype "passive"))
    )
    (net (code "37") (name "Net-(J1-SHLD-PadSHLD1)") (class "Default")
      (node (ref "J1") (pin "SHLD1") (pinfunction "SHLD_SHLD1") (pintype "bidirectional"))
      (node (ref "J1") (pin "SHLD2") (pinfunction "SHLD_SHLD2") (pintype "bidirectional"))
      (node (ref "J1") (pin "SHLD3") (pinfunction "SHLD_SHLD3") (pintype "bidirectional"))
      (node (ref "J1") (pin "SHLD4") (pinfunction "SHLD_SHLD4") (pintype "bidirectional"))
      (node (ref "J1") (pin "SHLD5") (pinfunction "SHLD_SHLD5") (pintype "bidirectional"))
      (node (ref "J1") (pin "SHLD6") (pinfunction "SHLD_SHLD6") (pintype "bidirectional"))
      (node (ref "J1") (pin "SHLD7") (pinfunction "SHLD_SHLD7") (pintype "bidirectional"))
      (node (ref "J1") (pin "SHLD8") (pinfunction "SHLD_SHLD8") (pintype "bidirectional"))
      (node (ref "SHLD") (pin "2") (pinfunction "2_2") (pintype "passive"))
    )
    (net (code "38") (name "Net-(JP4-Pad2)") (class "Default")
      (node (ref "JP4") (pin "2") (pinfunction "2_2") (pintype "passive"))
      (node (ref "R12") (pin "1") (pinfunction "1_1") (pintype "passive"))
    )
    (net (code "39") (name "Net-(Q1-G)") (class "Default")
      (node (ref "Q1") (pin "1") (pinfunction "G_1") (pintype "bidirectional"))
      (node (ref "R15") (pin "2") (pinfunction "2_2") (pintype "passive"))
    )
    (net (code "40") (name "Net-(Q2-G)") (class "Default")
      (node (ref "Q2") (pin "1") (pinfunction "G_1") (pintype "bidirectional"))
      (node (ref "R13") (pin "2") (pinfunction "2_2") (pintype "passive"))
    )
    (net (code "41") (name "Net-(RN1A-2)") (class "Default")
      (node (ref "RN1") (pin "16") (pinfunction "2_16") (pintype "passive"))
      (node (ref "U1") (pin "59") (pinfunction "P608/GTIOC4B_59") (pintype "bidirectional"))
    )
    (net (code "42") (name "Net-(RN1B-2)") (class "Default")
      (node (ref "RN1") (pin "15") (pinfunction "2_15") (pintype "passive"))
      (node (ref "U1") (pin "60") (pinfunction "P609/CTX1/GTIOC5A/AGTO5_60") (pintype "bidirectional"))
    )
    (net (code "43") (name "Net-(RN1C-2)") (class "Default")
      (node (ref "RN1") (pin "14") (pinfunction "2_14") (pintype "passive"))
      (node (ref "U1") (pin "61") (pinfunction "P610/CRX1/CTS7/GTIOC5B/AGTO4_61") (pintype "bidirectional"))
    )
    (net (code "44") (name "Net-(RN1D-2)") (class "Default")
      (node (ref "RN1") (pin "13") (pinfunction "2_13") (pintype "passive"))
      (node (ref "U1") (pin "67") (pinfunction "P600/SCK9/GTIOC6B_67") (pintype "bidirectional"))
    )
    (net (code "45") (name "Net-(RN1E-2)") (class "Default")
      (node (ref "RN1") (pin "12") (pinfunction "2_12") (pintype "passive"))
      (node (ref "U1") (pin "68") (pinfunction "P107/CTS8_RTS8_68") (pintype "bidirectional"))
    )
    (net (code "46") (name "Net-(RN1H-2)") (class "Default")
      (node (ref "RN1") (pin "9") (pinfunction "2_9") (pintype "passive"))
      (node (ref "U1") (pin "92") (pinfunction "P008/AN008_92") (pintype "bidirectional"))
    )
    (net (code "47") (name "Net-(RN3C-2)") (class "Default")
      (node (ref "RN3") (pin "14") (pinfunction "2_14") (pintype "passive"))
      (node (ref "U1") (pin "18") (pinfunction "P414/SDA2/CTS0/SSLB1_B/SD0WP_18") (pintype "bidirectional"))
    )
    (net (code "48") (name "Net-(RN3D-2)") (class "Default")
      (node (ref "RN3") (pin "13") (pinfunction "2_13") (pintype "passive"))
      (node (ref "U1") (pin "19") (pinfunction "P413/CTS0_RTS0/SSLB0_B/SD0CLK_A_19") (pintype "bidirectional"))
    )
    (net (code "49") (name "Net-(RN3E-2)") (class "Default")
      (node (ref "RN3") (pin "12") (pinfunction "2_12") (pintype "passive"))
      (node (ref "U1") (pin "20") (pinfunction "P412/SCK0/CTS3/RSPCKB_B_20") (pintype "bidirectional"))
    )
    (net (code "50") (name "Net-(RN3F-2)") (class "Default")
      (node (ref "RN3") (pin "11") (pinfunction "2_11") (pintype "passive"))
      (node (ref "U1") (pin "21") (pinfunction "P411/TXD0/CTS3_RTS3/PICOB_B_21") (pintype "bidirectional"))
    )
    (net (code "51") (name "Net-(RN3G-1)") (class "Default")
      (node (ref "C1") (pin "2") (pinfunction "2_2") (pintype "passive"))
      (node (ref "R1") (pin "1") (pinfunction "1_1") (pintype "passive"))
      (node (ref "RN3") (pin "7") (pinfunction "1_7") (pintype "passive"))
    )
    (net (code "52") (name "Net-(RN3G-2)") (class "Default")
      (node (ref "R2") (pin "2") (pinfunction "2_2") (pintype "passive"))
      (node (ref "RN3") (pin "10") (pinfunction "2_10") (pintype "passive"))
      (node (ref "U1") (pin "25") (pinfunction "P407/USB_VBUS/CTS4_RTS4_25") (pintype "bidirectional"))
    )
    (net (code "53") (name "Net-(RN3H-2)") (class "Default")
      (node (ref "RN3") (pin "9") (pinfunction "2_9") (pintype "passive"))
      (node (ref "U1") (pin "36") (pinfunction "P209/QIO2/SD0WP/GTOVUP_36") (pintype "bidirectional"))
    )
    (net (code "54") (name "Net-(RN4B-2)") (class "Default")
      (node (ref "RN4") (pin "15") (pinfunction "2_15") (pintype "passive"))
      (node (ref "U1") (pin "43") (pinfunction "P305/TXD6/QSPCLK/GTOWUP_43") (pintype "bidirectional"))
    )
    (net (code "55") (name "Net-(RN4C-2)") (class "Default")
      (node (ref "RN4") (pin "14") (pinfunction "2_14") (pintype "passive"))
      (node (ref "U1") (pin "42") (pinfunction "P306/SCK6/QSSL/GTOULO_D_42") (pintype "bidirectional"))
    )
    (net (code "56") (name "Net-(RN4D-2)") (class "Default")
      (node (ref "RN4") (pin "13") (pinfunction "2_13") (pintype "passive"))
      (node (ref "U1") (pin "41") (pinfunction "P307/CTS6_RTS6/QIO0/GTOUUP_D_41") (pintype "bidirectional"))
    )
    (net (code "57") (name "Net-(RN4E-2)") (class "Default")
      (node (ref "RN4") (pin "12") (pinfunction "2_12") (pintype "passive"))
      (node (ref "U1") (pin "48") (pinfunction "P302/TXD2/SSLA3_B/GTOUUP_48") (pintype "bidirectional"))
    )
    (net (code "58") (name "Net-(RN4F-2)") (class "Default")
      (node (ref "RN4") (pin "11") (pinfunction "2_11") (pintype "passive"))
      (node (ref "U1") (pin "56") (pinfunction "P113/RXD2/SSILRCK0_B/GTIOC2A_56") (pintype "bidirectional"))
    )
    (net (code "59") (name "Net-(RN4G-2)") (class "Default")
      (node (ref "RN4") (pin "10") (pinfunction "2_10") (pintype "passive"))
      (node (ref "U1") (pin "57") (pinfunction "P114/CTS9/SSIRXD0_B/GTIOC2B_57") (pintype "bidirectional"))
    )
    (net (code "60") (name "Net-(RN5C-1)") (class "Default")
      (node (ref "RN5") (pin "3") (pinfunction "1_3") (pintype "passive"))
      (node (ref "U1") (pin "98") (pinfunction "P002/AN002/AN102_98") (pintype "bidirectional"))
    )
    (net (code "61") (name "Net-(RN5D-1)") (class "Default")
      (node (ref "RN5") (pin "4") (pinfunction "1_4") (pintype "passive"))
      (node (ref "U1") (pin "97") (pinfunction "P003/AN003_97") (pintype "bidirectional"))
    )
    (net (code "62") (name "Net-(RN5E-1)") (class "Default")
      (node (ref "RN5") (pin "5") (pinfunction "1_5") (pintype "passive"))
      (node (ref "U1") (pin "96") (pinfunction "P004/AN004_96") (pintype "bidirectional"))
    )
    (net (code "63") (name "Net-(RN5F-1)") (class "Default")
      (node (ref "RN5") (pin "6") (pinfunction "1_6") (pintype "passive"))
      (node (ref "U1") (pin "95") (pinfunction "P005/AN005_95") (pintype "bidirectional"))
    )
    (net (code "64") (name "Net-(RN5G-1)") (class "Default")
      (node (ref "RN5") (pin "7") (pinfunction "1_7") (pintype "passive"))
      (node (ref "U1") (pin "94") (pinfunction "P006/AN006_94") (pintype "bidirectional"))
    )
    (net (code "65") (name "Net-(RN5H-1)") (class "Default")
      (node (ref "RN5") (pin "8") (pinfunction "1_8") (pintype "passive"))
      (node (ref "U1") (pin "93") (pinfunction "P007/AN007_93") (pintype "bidirectional"))
    )
    (net (code "66") (name "Net-(U1B-VREFH)") (class "Default")
      (node (ref "C26") (pin "1") (pinfunction "1_1") (pintype "passive"))
      (node (ref "C27") (pin "1") (pinfunction "1_1") (pintype "passive"))
      (node (ref "FB2") (pin "1") (pinfunction "1_1") (pintype "passive"))
      (node (ref "U1") (pin "87") (pinfunction "VREFH_87") (pintype "bidirectional"))
      (node (ref "U1") (pin "91") (pinfunction "VREFH0_91") (pintype "bidirectional"))
    )
    (net (code "67") (name "Net-(U1C-VBATT)") (class "Default")
      (node (ref "BAT") (pin "2") (pinfunction "2_2") (pintype "passive"))
      (node (ref "U1") (pin "8") (pinfunction "VBATT_8") (pintype "bidirectional"))
    )
    (net (code "68") (name "Net-(U1C-VCL)") (class "Default")
      (node (ref "C12") (pin "1") (pinfunction "1_1") (pintype "passive"))
      (node (ref "U1") (pin "64") (pinfunction "VCL_64") (pintype "bidirectional"))
    )
    (net (code "69") (name "Net-(U1C-VCL0)") (class "Default")
      (node (ref "C11") (pin "1") (pinfunction "1_1") (pintype "passive"))
      (node (ref "U1") (pin "9") (pinfunction "VCL0_9") (pintype "bidirectional"))
    )
    (net (code "70") (name "Net-(U1H-P212{slash}EXTAL{slash}RXD1)") (class "Default")
      (node (ref "U1") (pin "14") (pinfunction "P212/EXTAL/RXD1_14") (pintype "bidirectional"))
      (node (ref "Y1") (pin "1") (pinfunction "1_1") (pintype "passive"))
    )
    (net (code "71") (name "Net-(U1H-P213{slash}XTAL{slash}TXD1)") (class "Default")
      (node (ref "U1") (pin "13") (pinfunction "P213/XTAL/TXD1_13") (pintype "bidirectional"))
      (node (ref "Y1") (pin "3") (pinfunction "2_3") (pintype "passive"))
    )
    (net (code "72") (name "Net-(U1H-XCIN)") (class "Default")
      (node (ref "C10") (pin "2") (pinfunction "2_2") (pintype "passive"))
      (node (ref "U1") (pin "10") (pinfunction "XCIN_10") (pintype "bidirectional"))
      (node (ref "Y2") (pin "P$1") (pinfunction "1_P$1") (pintype "passive"))
    )
    (net (code "73") (name "Net-(U1H-XCOUT)") (class "Default")
      (node (ref "C9") (pin "2") (pinfunction "2_2") (pintype "passive"))
      (node (ref "U1") (pin "11") (pinfunction "XCOUT_11") (pintype "bidirectional"))
      (node (ref "Y2") (pin "P$2") (pinfunction "2_P$2") (pintype "passive"))
    )
    (net (code "74") (name "Net-(U3-PROG)") (class "Default")
      (node (ref "R11") (pin "2") (pinfunction "2_2") (pintype "passive"))
      (node (ref "U3") (pin "5") (pinfunction "PROG_5") (pintype "input"))
    )
    (net (code "75") (name "Net-(U3-STAT)") (class "Default")
      (node (ref "D5") (pin "C") (pinfunction "C_C") (pintype "passive"))
      (node (ref "U3") (pin "1") (pinfunction "STAT_1") (pintype "output"))
    )
    (net (code "76") (name "QIO0") (class "Default")
      (node (ref "U1") (pin "73") (pinfunction "P102/QIO0/SCK0/RSPCKB_A_73") (pintype "bidirectional"))
      (node (ref "U5") (pin "5") (pinfunction "D0/DI_5") (pintype "bidirectional"))
    )
    (net (code "77") (name "QIO1") (class "Default")
      (node (ref "U1") (pin "74") (pinfunction "P101/QIO1/TXD0/CTS1_RTS1/PICOB_A_74") (pintype "bidirectional"))
      (node (ref "U5") (pin "2") (pinfunction "D1/DO_2") (pintype "bidirectional"))
    )
    (net (code "78") (name "QIO2") (class "Default")
      (node (ref "U1") (pin "71") (pinfunction "P104/QIO2/RXD8/SSLB1_A_71") (pintype "bidirectional"))
      (node (ref "U5") (pin "3") (pinfunction "D2/~{WP}_3") (pintype "bidirectional"))
    )
    (net (code "79") (name "QIO3") (class "Default")
      (node (ref "U1") (pin "72") (pinfunction "P103/QIO3/SSLB0_A/CTS0_RTS0_72") (pintype "bidirectional"))
      (node (ref "U5") (pin "7") (pinfunction "D3/~{RESET}_7") (pintype "bidirectional"))
    )
    (net (code "80") (name "QSPCLK") (class "Default")
      (node (ref "U1") (pin "75") (pinfunction "P100/QSPCLK/RXD0/SCK1/POCIB_A_75") (pintype "bidirectional"))
      (node (ref "U5") (pin "6") (pinfunction "CLK_6") (pintype "bidirectional"))
    )
    (net (code "81") (name "RA6_SWCLK{slash}TCK") (class "Default")
      (node (ref "J4") (pin "3") (pinfunction "3_3") (pintype "bidirectional"))
      (node (ref "U1") (pin "50") (pinfunction "P300/TCK/SWCLK/SSLA1_B_50") (pintype "bidirectional"))
    )
    (net (code "82") (name "RA6_SWDIO{slash}TMS") (class "Default")
      (node (ref "J4") (pin "2") (pinfunction "2_2") (pintype "bidirectional"))
      (node (ref "U1") (pin "51") (pinfunction "P108/TMS/SWDIO/CTS9_RTS9_51") (pintype "bidirectional"))
    )
    (net (code "83") (name "RA6_SWO{slash}TDO{slash}PICO{slash}D18") (class "Default")
      (node (ref "J2") (pin "17") (pinfunction "PICO_17") (pintype "bidirectional"))
      (node (ref "J4") (pin "4") (pinfunction "4_4") (pintype "bidirectional"))
      (node (ref "U1") (pin "52") (pinfunction "P109/TDO/SWO/PICOA_B/TXD9_52") (pintype "bidirectional"))
    )
    (net (code "84") (name "RA6_TDI{slash}POCI{slash}D17") (class "Default")
      (node (ref "J2") (pin "16") (pinfunction "POCI_16") (pintype "bidirectional"))
      (node (ref "U1") (pin "53") (pinfunction "P110/TDI/POCIA_B/CTS2_RTS2/RXD9_53") (pintype "bidirectional"))
    )
    (net (code "85") (name "RGB_DIN") (class "Default")
      (node (ref "D4") (pin "DI") (pinfunction "DI_DI") (pintype "bidirectional"))
      (node (ref "U1") (pin "70") (pinfunction "P105/TXD8/SSLB2_A_70") (pintype "bidirectional"))
    )
    (net (code "86") (name "RGB_DOUT") (class "Default")
      (node (ref "D4") (pin "DO") (pinfunction "DO_DO") (pintype "bidirectional"))
      (node (ref "TP1") (pin "1") (pinfunction "1_1") (pintype "bidirectional"))
    )
    (net (code "87") (name "RX_RA6{slash}TX_DA14531") (class "Default")
      (node (ref "TP6") (pin "1") (pinfunction "1_1") (pintype "bidirectional"))
      (node (ref "U1") (pin "66") (pinfunction "P601/RXD9/GTIOC6A_66") (pintype "bidirectional"))
      (node (ref "U2") (pin "5") (pinfunction "P0_6/UTX_5") (pintype "bidirectional"))
    )
    (net (code "88") (name "SCK{slash}D19") (class "Default")
      (node (ref "J2") (pin "18") (pinfunction "SCK_18") (pintype "bidirectional"))
      (node (ref "U1") (pin "54") (pinfunction "P111/RSPCKA_B/SCK2/SCK9_54") (pintype "bidirectional"))
    )
    (net (code "89") (name "SCL{slash}D16") (class "Default")
      (node (ref "J2") (pin "2") (pinfunction "SCL_2") (pintype "bidirectional"))
      (node (ref "J3") (pin "4") (pinfunction "4_4") (pintype "passive"))
      (node (ref "R7") (pin "1") (pinfunction "1_1") (pintype "passive"))
      (node (ref "U1") (pin "1") (pinfunction "P400/SCL0_A/SCK4/SCK7/AUDIO_CLK_1") (pintype "bidirectional"))
      (node (ref "U7") (pin "7") (pinfunction "SCL_7") (pintype "output"))
    )
    (net (code "90") (name "SDA{slash}D15") (class "Default")
      (node (ref "J2") (pin "1") (pinfunction "SDA_1") (pintype "bidirectional"))
      (node (ref "J3") (pin "3") (pinfunction "3_3") (pintype "passive"))
      (node (ref "R6") (pin "1") (pinfunction "1_1") (pintype "passive"))
      (node (ref "U1") (pin "2") (pinfunction "P401/SDA0_A/TXD7/CTS4_RTS4_2") (pintype "bidirectional"))
      (node (ref "U7") (pin "8") (pinfunction "SDA_8") (pintype "input"))
    )
    (net (code "91") (name "SDCLK") (class "Default")
      (node (ref "J7") (pin "5") (pinfunction "CLK/SCK_5") (pintype "bidirectional"))
      (node (ref "U1") (pin "33") (pinfunction "P214/SD0CLK_B/QSPCLK_33") (pintype "bidirectional"))
    )
    (net (code "92") (name "SDCMD") (class "Default")
      (node (ref "J7") (pin "3") (pinfunction "CMD/SDI_3") (pintype "bidirectional"))
      (node (ref "U1") (pin "34") (pinfunction "P211/SD0CMD_B/QIO0_34") (pintype "bidirectional"))
    )
    (net (code "93") (name "SDDAT0") (class "Default")
      (node (ref "J7") (pin "7") (pinfunction "DAT0/SDO_7") (pintype "bidirectional"))
      (node (ref "U1") (pin "37") (pinfunction "P208/SD0DAT0_B/QIO3_37") (pintype "bidirectional"))
    )
    (net (code "94") (name "SDDAT1") (class "Default")
      (node (ref "J7") (pin "8") (pinfunction "DAT1_8") (pintype "bidirectional"))
      (node (ref "U1") (pin "22") (pinfunction "P410/SD0DAT1_A/RXD0/SCL2/SCK3_22") (pintype "bidirectional"))
    )
    (net (code "95") (name "SDDAT2") (class "Default")
      (node (ref "J7") (pin "1") (pinfunction "DAT2_1") (pintype "bidirectional"))
      (node (ref "U1") (pin "31") (pinfunction "P206/SD0DAT2_A/USB_VBUSEN/RXD4_31") (pintype "bidirectional"))
    )
    (net (code "96") (name "SDDAT3") (class "Default")
      (node (ref "J7") (pin "2") (pinfunction "DAT3/~{CS}_2") (pintype "bidirectional"))
      (node (ref "U1") (pin "32") (pinfunction "P205/SD0DAT3_A/TXD4/CTS9_RTS9_32") (pintype "bidirectional"))
    )
    (net (code "97") (name "SDDET") (class "Default")
      (node (ref "J7") (pin "9") (pinfunction "DET_9") (pintype "bidirectional"))
      (node (ref "U1") (pin "35") (pinfunction "P210/SD0CD/QIO1_35") (pintype "bidirectional"))
    )
    (net (code "98") (name "STAT_LED") (class "Default")
      (node (ref "D2") (pin "A") (pinfunction "A_A") (pintype "passive"))
      (node (ref "U1") (pin "69") (pinfunction "P106/SCK8/SSLB3_A_69") (pintype "bidirectional"))
    )
    (net (code "99") (name "TX_RA6{slash}RX_DA14531") (class "Default")
      (node (ref "TP5") (pin "1") (pinfunction "1_1") (pintype "bidirectional"))
      (node (ref "U1") (pin "65") (pinfunction "P602/TXD9/GTIOC7B_65") (pintype "bidirectional"))
      (node (ref "U2") (pin "14") (pinfunction "P0_5/URX_14") (pintype "bidirectional"))
    )
    (net (code "100") (name "UART_RX{slash}D21") (class "Default")
      (node (ref "J2") (pin "15") (pinfunction "RX_15") (pintype "bidirectional"))
      (node (ref "U1") (pin "24") (pinfunction "P408/RXD3/SCL0_B/USB_ID_24") (pintype "bidirectional"))
    )
    (net (code "101") (name "UART_TX{slash}D20") (class "Default")
      (node (ref "J2") (pin "14") (pinfunction "TX_14") (pintype "bidirectional"))
      (node (ref "U1") (pin "23") (pinfunction "P409/TXD3/SDA2/USB_EXICEN_23") (pintype "bidirectional"))
    )
    (net (code "102") (name "USBD_N") (class "Default")
      (node (ref "D1") (pin "4") (pinfunction "4_4") (pintype "bidirectional"))
      (node (ref "U1") (pin "27") (pinfunction "USB_DM_27") (pintype "bidirectional"))
    )
    (net (code "103") (name "USBD_P") (class "Default")
      (node (ref "D1") (pin "6") (pinfunction "6_6") (pintype "bidirectional"))
      (node (ref "U1") (pin "28") (pinfunction "USB_DP_28") (pintype "bidirectional"))
    )
    (net (code "104") (name "VIN") (class "Default")
      (node (ref "C14") (pin "1") (pinfunction "1_1") (pintype "passive"))
      (node (ref "C17") (pin "1") (pinfunction "1_1") (pintype "passive"))
      (node (ref "C20") (pin "1") (pinfunction "1_1") (pintype "passive"))
      (node (ref "R10") (pin "2") (pinfunction "2_2") (pintype "passive"))
      (node (ref "U4") (pin "1") (pinfunction "IN_1") (pintype "input"))
      (node (ref "U6") (pin "1") (pinfunction "IN_1") (pintype "input"))
      (node (ref "U8") (pin "2") (pinfunction "VOUT_2") (pintype "bidirectional"))
      (node (ref "U8") (pin "7") (pinfunction "VOUT_7") (pintype "bidirectional"))
    )
    (net (code "105") (name "VREF1") (class "Default")
      (node (ref "C19") (pin "1") (pinfunction "1_1") (pintype "passive"))
      (node (ref "FB2") (pin "2") (pinfunction "2_2") (pintype "passive"))
      (node (ref "J2") (pin "26") (pinfunction "AREF/NC_26") (pintype "bidirectional"))
      (node (ref "U6") (pin "5") (pinfunction "OUT_5") (pintype "passive"))
    )
    (net (code "106") (name "VREFEN") (class "Default")
      (node (ref "RN1") (pin "6") (pinfunction "1_6") (pintype "passive"))
      (node (ref "TP2") (pin "1") (pinfunction "1_1") (pintype "bidirectional"))
      (node (ref "U1") (pin "76") (pinfunction "P500/USB_VBUSEN/CTS5/QSPCLK_76") (pintype "bidirectional"))
      (node (ref "U6") (pin "3") (pinfunction "EN_3") (pintype "input"))
    )
    (net (code "107") (name "VREG_EN") (class "Default")
      (node (ref "J2") (pin "11") (pinfunction "EN_11") (pintype "bidirectional"))
      (node (ref "R10") (pin "1") (pinfunction "1_1") (pintype "passive"))
      (node (ref "U4") (pin "3") (pinfunction "EN_3") (pintype "input"))
    )
    (net (code "108") (name "V_BATT") (class "Default")
      (node (ref "C15") (pin "1") (pinfunction "1_1") (pintype "passive"))
      (node (ref "C18") (pin "2") (pinfunction "2_2") (pintype "passive"))
      (node (ref "J2") (pin "12") (pinfunction "V_BATT_12") (pintype "bidirectional"))
      (node (ref "J6") (pin "2") (pinfunction "+_2") (pintype "bidirectional"))
      (node (ref "U3") (pin "3") (pinfunction "VBAT_3") (pintype "power_in"))
      (node (ref "U7") (pin "2") (pinfunction "CELL_2") (pintype "input"))
      (node (ref "U7") (pin "3") (pinfunction "VDD_3") (pintype "bidirectional"))
      (node (ref "U8") (pin "3") (pinfunction "VIN1_3") (pintype "bidirectional"))
    )
    (net (code "109") (name "V_USB") (class "Default")
      (node (ref "C13") (pin "1") (pinfunction "1_1") (pintype "passive"))
      (node (ref "D1") (pin "5") (pinfunction "5_5") (pintype "power_in"))
      (node (ref "J1") (pin "VBUS1") (pinfunction "VBUS_VBUS1") (pintype "bidirectional"))
      (node (ref "J1") (pin "VBUS2") (pinfunction "VBUS_VBUS2") (pintype "bidirectional"))
      (node (ref "J2") (pin "10") (pinfunction "V_USB_10") (pintype "bidirectional"))
      (node (ref "R1") (pin "2") (pinfunction "2_2") (pintype "passive"))
      (node (ref "R9") (pin "2") (pinfunction "2_2") (pintype "passive"))
      (node (ref "U3") (pin "4") (pinfunction "VIN_4") (pintype "power_in"))
      (node (ref "U8") (pin "6") (pinfunction "VIN2_6") (pintype "bidirectional"))
    )
    (net (code "110") (name "unconnected-(J6-PAD1-PadNC1)") (class "Default")
      (node (ref "J6") (pin "NC1") (pinfunction "PAD1_NC1") (pintype "bidirectional"))
    )
    (net (code "111") (name "unconnected-(J6-PAD2-PadNC2)") (class "Default")
      (node (ref "J6") (pin "NC2") (pinfunction "PAD2_NC2") (pintype "bidirectional"))
    )
    (net (code "112") (name "~{CTS_RA6{slash}RTS_DA14531}") (class "Default")
      (node (ref "TP7") (pin "1") (pinfunction "1_1") (pintype "bidirectional"))
      (node (ref "U1") (pin "47") (pinfunction "P303/CTS9/GTIOC7B_47") (pintype "bidirectional"))
      (node (ref "U2") (pin "13") (pinfunction "P0_7/URTS_13") (pintype "bidirectional"))
    )
    (net (code "113") (name "~{DA14531_RST}") (class "Default")
      (node (ref "J5") (pin "6") (pinfunction "6_6") (pintype "bidirectional"))
      (node (ref "R13") (pin "1") (pinfunction "1_1") (pintype "passive"))
      (node (ref "R16") (pin "2") (pinfunction "2_2") (pintype "passive"))
      (node (ref "U1") (pin "58") (pinfunction "P115/SSITXD0_B/GTIOC4A_58") (pintype "bidirectional"))
    )
    (net (code "114") (name "~{FG_ALRT}") (class "Default")
      (node (ref "RN5") (pin "1") (pinfunction "1_1") (pintype "passive"))
      (node (ref "U1") (pin "100") (pinfunction "P000/AN000/AN100_100") (pintype "bidirectional"))
      (node (ref "U7") (pin "5") (pinfunction "~{ALRT}_5") (pintype "bidirectional"))
    )
    (net (code "115") (name "~{NMI}") (class "Default")
      (node (ref "RN4") (pin "16") (pinfunction "2_16") (pintype "passive"))
      (node (ref "TP9") (pin "1") (pinfunction "1_1") (pintype "bidirectional"))
      (node (ref "U1") (pin "40") (pinfunction "P200/NMI_40") (pintype "bidirectional"))
    )
    (net (code "116") (name "~{QCS}") (class "Default")
      (node (ref "RN1") (pin "7") (pinfunction "1_7") (pintype "passive"))
      (node (ref "U1") (pin "77") (pinfunction "P501/QSSL/TXD5/USB_OVRCURA_77") (pintype "bidirectional"))
      (node (ref "U5") (pin "1") (pinfunction "~{CS}_1") (pintype "bidirectional"))
    )
    (net (code "117") (name "~{RA6M5_RESET}") (class "Default")
      (node (ref "J2") (pin "28") (pinfunction "~{RESET}_28") (pintype "bidirectional"))
      (node (ref "J4") (pin "6") (pinfunction "6_6") (pintype "bidirectional"))
      (node (ref "R14") (pin "1") (pinfunction "1_1") (pintype "passive"))
      (node (ref "S2") (pin "3") (pinfunction "2_3") (pintype "passive"))
      (node (ref "S2") (pin "4") (pinfunction "2_4") (pintype "passive"))
      (node (ref "U1") (pin "38") (pinfunction "~{RES}_38") (pintype "bidirectional"))
      (node (ref "U2") (pin "8") (pinfunction "P0_11_8") (pintype "bidirectional"))
    )
    (net (code "118") (name "~{RTS_RA6{slash}CTS_DA14531}") (class "Default")
      (node (ref "TP8") (pin "1") (pinfunction "1_1") (pintype "bidirectional"))
      (node (ref "U1") (pin "49") (pinfunction "P301/CTS9_RTS9/RXD2/SSLA2_B_49") (pintype "bidirectional"))
      (node (ref "U2") (pin "16") (pinfunction "P0_8/UCTS_16") (pintype "bidirectional"))
    )
    (net (code "119") (name "~{SD_EN}") (class "Default")
      (node (ref "R15") (pin "1") (pinfunction "1_1") (pintype "passive"))
      (node (ref "RN3") (pin "16") (pinfunction "2_16") (pintype "passive"))
      (node (ref "U1") (pin "16") (pinfunction "P708/AUDIO_CLK/RXD1/CECIO_16") (pintype "bidirectional"))
    )
    (net (code "120") (name "~{USR_BTN}") (class "Default")
      (node (ref "RN3") (pin "15") (pinfunction "2_15") (pintype "passive"))
      (node (ref "S1") (pin "1") (pinfunction "1_1") (pintype "passive"))
      (node (ref "S1") (pin "2") (pinfunction "1_2") (pintype "passive"))
      (node (ref "U1") (pin "17") (pinfunction "P415/USB_VBUSEN/SCL2/SSLB2_B_17") (pintype "bidirectional"))
    )
  )
)
